# DC_Power_Switching.net
KiCad netlist of a schematic drawn in Altium Designer
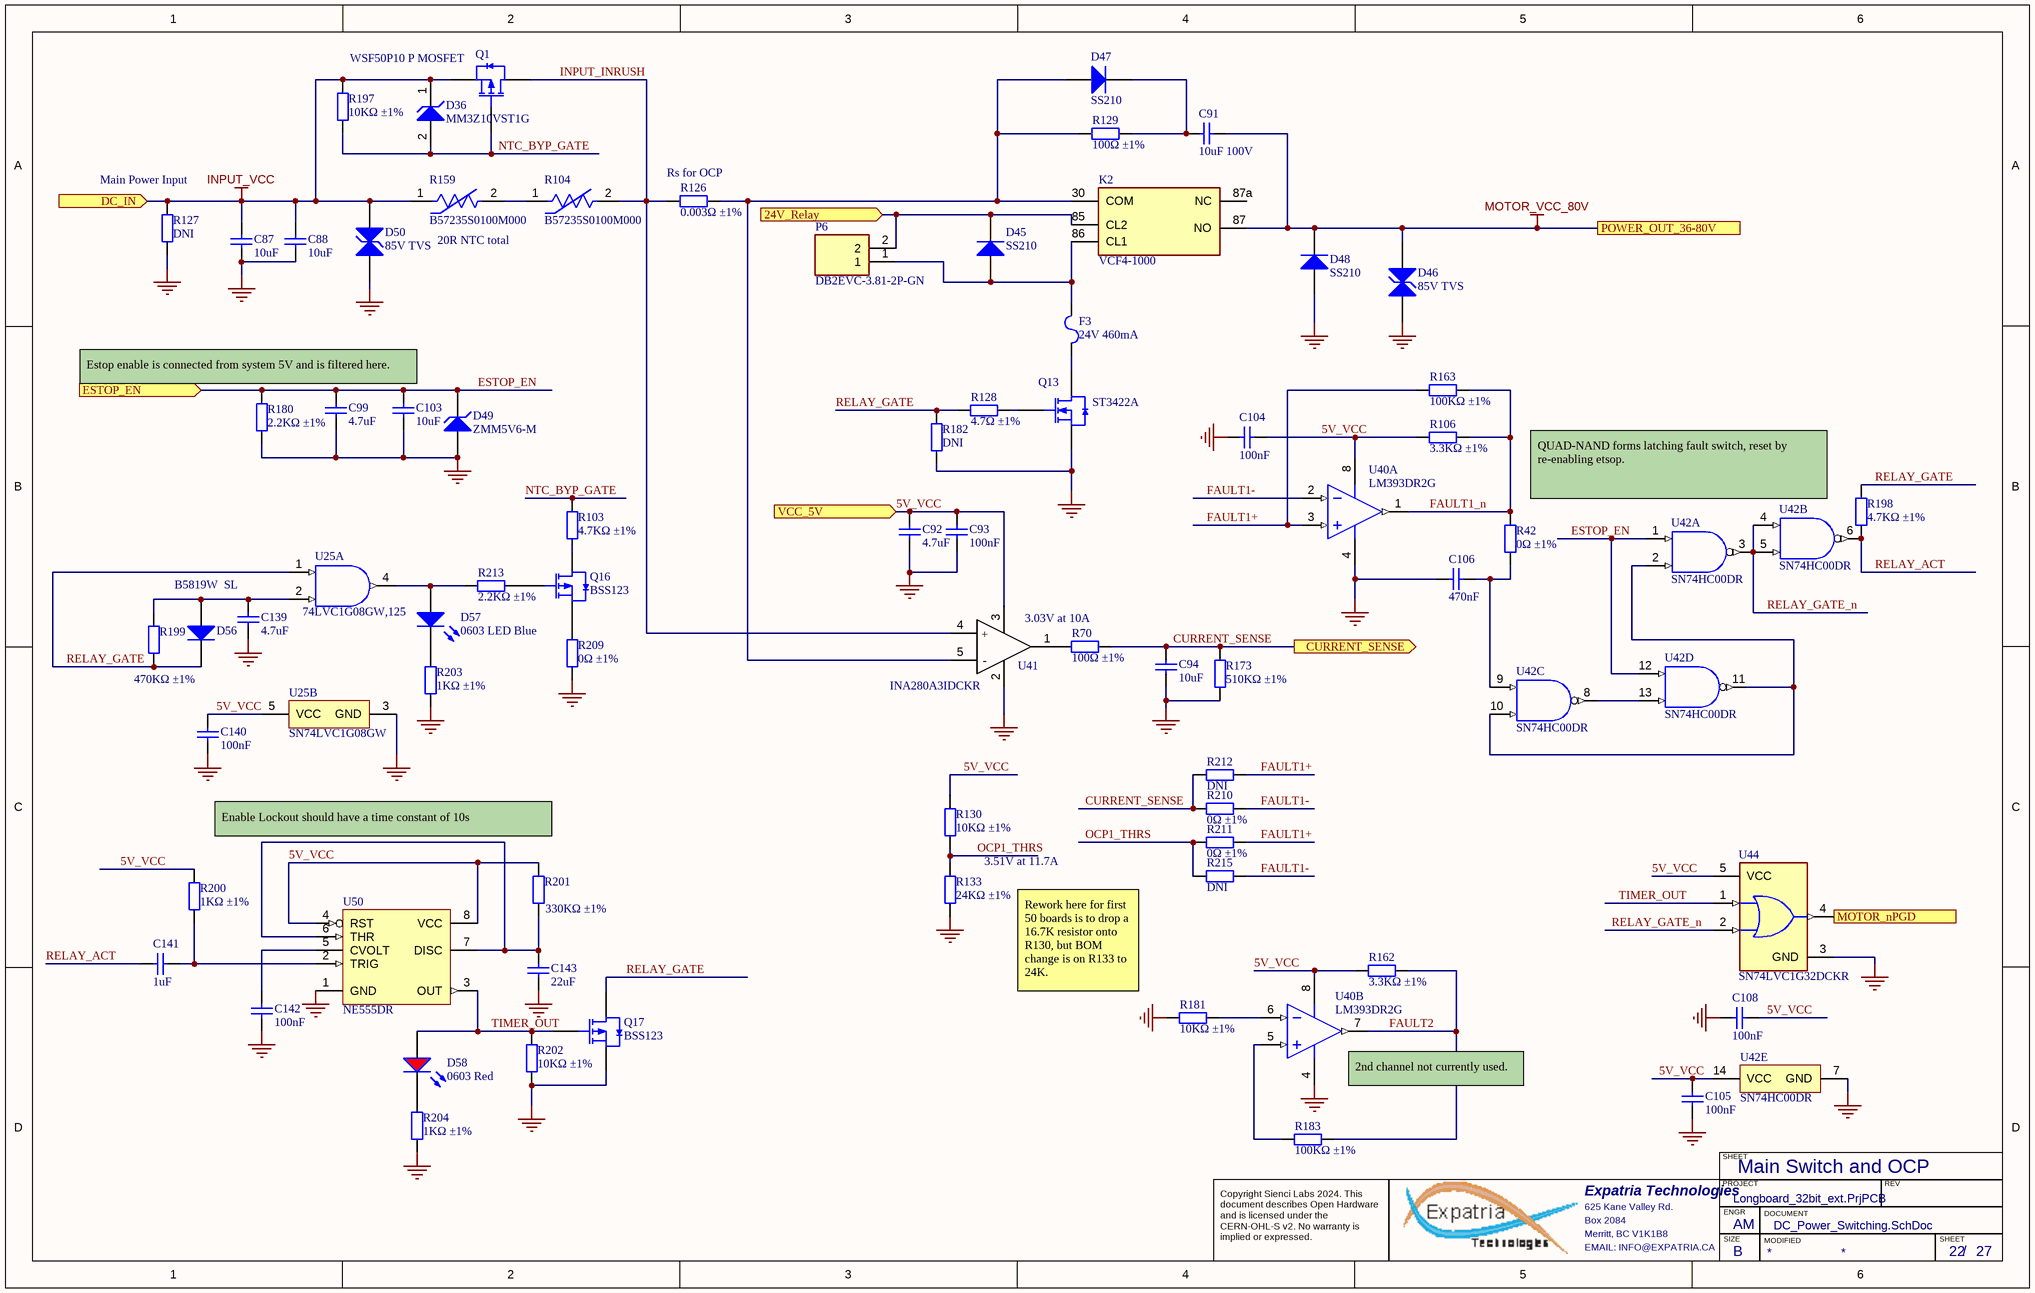
[diagram p0: DC_Power_Switching.SchDoc]

(export (version "E")
  (design (tool "Eeschema 10.0.6"))
  (components
    (comp (ref "C87")
      (value "10uF")
      (footprint "1206_C")
      (description "50V 10uF X5R ±10% 1206 Multilayer Ceramic Capacitors MLCC - SMD/SMT ROHS")
      (fields (field (name "MANUFACTURER") "Samsung Electro-Mechanics") (field (name "TOLERANCE") "10%"))
      (libsource (lib "Sienci_Labs") (part "1206 10uF (106) 10% 50V"))
    )
    (comp (ref "C88")
      (value "10uF")
      (footprint "1206_C")
      (description "50V 10uF X5R ±10% 1206 Multilayer Ceramic Capacitors MLCC - SMD/SMT ROHS")
      (fields (field (name "MANUFACTURER") "Samsung Electro-Mechanics") (field (name "TOLERANCE") "10%"))
      (libsource (lib "Sienci_Labs") (part "1206 10uF (106) 10% 50V"))
    )
    (comp (ref "C91")
      (value "10uF 100V")
      (footprint "1210_C")
      (description "Chip capacitors")
      (fields (field (name "MANUFACTURER") "Murata") (field (name "TOLERANCE") "10%"))
      (libsource (lib "Sienci_Labs") (part "1210 10uF (106) 10% 100V"))
    )
    (comp (ref "C92")
      (value "4.7uF")
      (footprint "0603_C")
      (description "16V 4.7uF X5R ±10% 0603 Multilayer Ceramic Capacitors MLCC - SMD/SMT ROHS")
      (fields (field (name "MANUFACTURER") "Samsung Electro-Mechanics") (field (name "TOLERANCE") "10%"))
      (libsource (lib "Sienci_Labs") (part "0603 4.7uF (475) 10% 16V"))
    )
    (comp (ref "C93")
      (value "100nF")
      (footprint "0603_C")
      (description "50V 100nF X7R ±10% 0603 Multilayer Ceramic Capacitors MLCC - SMD/SMT ROHS")
      (fields
        (field (name "MANUFACTURER") "YAGEO")
        (field (name "MANUFACTURER PART NUMBER") "CC0603KRX7R9BB104")
      )
      (libsource (lib "Sienci_Labs") (part "0603 100nF (104) 10% 50V"))
    )
    (comp (ref "C94")
      (value "10uF")
      (footprint "0603_C")
      (description "Chip capacitors")
      (fields (field (name "MANUFACTURER") "Samsung Electro-Mechanics") (field (name "TOLERANCE") "10%"))
      (libsource (lib "Cap") (part "0603 10uF (106) 10% 10V"))
    )
    (comp (ref "C99")
      (value "4.7uF")
      (footprint "0603_C")
      (description "16V 4.7uF X5R ±10% 0603 Multilayer Ceramic Capacitors MLCC - SMD/SMT ROHS")
      (fields (field (name "MANUFACTURER") "Samsung Electro-Mechanics") (field (name "TOLERANCE") "10%"))
      (libsource (lib "Sienci_Labs") (part "0603 4.7uF (475) 10% 16V"))
    )
    (comp (ref "C103")
      (value "10uF")
      (footprint "0603_C")
      (description "Chip capacitors")
      (fields
        (field (name "MANUFACTURER") "Samsung Electro-Mechanics")
        (field (name "MANUFACTURER PART NUMBER") "CL10A106KP8NNNC")
      )
      (libsource (lib "Cap") (part "0603 10uF (106) 10% 10V"))
    )
    (comp (ref "C104")
      (value "100nF")
      (footprint "0603_C")
      (description "50V 100nF X7R ±10% 0603 Multilayer Ceramic Capacitors MLCC - SMD/SMT ROHS")
      (fields
        (field (name "MANUFACTURER") "YAGEO")
        (field (name "MANUFACTURER PART NUMBER") "CC0603KRX7R9BB104")
      )
      (libsource (lib "Sienci_Labs") (part "0603 100nF (104) 10% 50V"))
    )
    (comp (ref "C105")
      (value "100nF")
      (footprint "0603_C")
      (description "50V 100nF X7R ±10% 0603 Multilayer Ceramic Capacitors MLCC - SMD/SMT ROHS")
      (fields
        (field (name "MANUFACTURER") "YAGEO")
        (field (name "MANUFACTURER PART NUMBER") "CC0603KRX7R9BB104")
      )
      (libsource (lib "Sienci_Labs") (part "0603 100nF (104) 10% 50V"))
    )
    (comp (ref "C106")
      (value "470nF")
      (footprint "0603_C")
      (description "Chip capacitors")
      (fields (field (name "MANUFACTURER") "Samsung Electro-Mechanics") (field (name "TOLERANCE") "10%"))
      (libsource (lib "Cap") (part "0603 470nF (474) 10% 25V"))
    )
    (comp (ref "C108")
      (value "100nF")
      (footprint "0603_C")
      (description "50V 100nF X7R ±10% 0603 Multilayer Ceramic Capacitors MLCC - SMD/SMT ROHS")
      (fields
        (field (name "MANUFACTURER") "YAGEO")
        (field (name "MANUFACTURER PART NUMBER") "CC0603KRX7R9BB104")
      )
      (libsource (lib "Sienci_Labs") (part "0603 100nF (104) 10% 50V"))
    )
    (comp (ref "C139")
      (value "4.7uF")
      (footprint "1206_C")
      (description "Chip capacitors")
      (fields
        (field (name "MANUFACTURER") "Guangdong Fenghua Advanced Tech")
        (field (name "MANUFACTURER PART NUMBER") "1206B475K500NT")
      )
      (libsource (lib "Cap") (part "1206 4.7uF (475) 10% 50V"))
    )
    (comp (ref "C140")
      (value "100nF")
      (footprint "0603_C")
      (description "50V 100nF X7R ±10% 0603 Multilayer Ceramic Capacitors MLCC - SMD/SMT ROHS")
      (fields
        (field (name "MANUFACTURER") "YAGEO")
        (field (name "MANUFACTURER PART NUMBER") "CC0603KRX7R9BB104")
      )
      (libsource (lib "Sienci_Labs") (part "0603 100nF (104) 10% 50V"))
    )
    (comp (ref "C141")
      (value "1uF")
      (footprint "0603_C")
      (description "Chip capacitors")
      (fields (field (name "MANUFACTURER") "Samsung Electro-Mechanics") (field (name "TOLERANCE") "10%"))
      (libsource (lib "Cap") (part "0603 1uF (105) 10% 50V"))
    )
    (comp (ref "C142")
      (value "100nF")
      (footprint "0603_C")
      (description "50V 100nF X7R ±10% 0603 Multilayer Ceramic Capacitors MLCC - SMD/SMT ROHS")
      (fields
        (field (name "MANUFACTURER") "YAGEO")
        (field (name "MANUFACTURER PART NUMBER") "CC0603KRX7R9BB104")
      )
      (libsource (lib "Sienci_Labs") (part "0603 100nF (104) 10% 50V"))
    )
    (comp (ref "C143")
      (value "22uF")
      (footprint "1206_C")
      (description "Chip capacitors")
      (fields
        (field (name "MANUFACTURER") "Samsung")
        (field (name "MANUFACTURER PART NUMBER") "CL31A226KAHNNNE")
      )
      (libsource (lib "Cap") (part "1206 4.7uF (475) 10% 50V"))
    )
    (comp (ref "D36")
      (value "MM3Z10VST1G")
      (footprint "ONSC-SOD-323-2-477-02_V")
      (description "MM3Z10VST1G Zener Diode, 10V 2% 300 mW SMT 2-Pin SOD-323 ¦ ON Semiconductor MM3Z10VST1G")
      (fields (field (name "MANUFACTURER") "On Semiconductor") (field (name "TOLERANCE") "2%"))
      (libsource (lib "Sienci_Labs") (part "MM3Z10VST1G"))
    )
    (comp (ref "D45")
      (value "SS210")
      (footprint "SMA(DO-214AC)_S1")
      (description "100V 2A 850mV @ 2A SMA(DO-214AC) Schottky Barrier Diodes (SBD) ROHS")
      (fields (field (name "MANUFACTURER") "MDD(Microdiode Electronics)"))
      (libsource (lib "Diode") (part "SMA(DO-214AC) SS210"))
    )
    (comp (ref "D46")
      (value "85V TVS")
      (footprint "SMB(DO-214AA)_S1")
      (description "4.4A 137V 94.4V 85V DO-214AA Electrostatic and Surge Protection (TVS/ESD) ROHS")
      (fields (field (name "MANUFACTURER") "BORN") (field (name "MANUFACTURER PART NUMBER") "SMBJ85CA"))
      (libsource (lib "Sienci_Labs") (part "SMBJ85CA"))
    )
    (comp (ref "D47")
      (value "SS210")
      (footprint "SMA(DO-214AC)_S1")
      (description "100V 2A 850mV @ 2A SMA(DO-214AC) Schottky Barrier Diodes (SBD) ROHS")
      (fields (field (name "MANUFACTURER") "MDD(Microdiode Electronics)"))
      (libsource (lib "Diode") (part "SMA(DO-214AC) SS210"))
    )
    (comp (ref "D48")
      (value "SS210")
      (footprint "SMA(DO-214AC)_S1")
      (description "100V 2A 850mV @ 2A SMA(DO-214AC) Schottky Barrier Diodes (SBD) ROHS")
      (fields (field (name "MANUFACTURER") "MDD(Microdiode Electronics)"))
      (libsource (lib "Diode") (part "SMA(DO-214AC) SS210"))
    )
    (comp (ref "D49")
      (value "ZMM5V6-M")
      (footprint "LL-34")
      (description "Single 500mW 5.2V~6V 5.6V LL-34 Zener Diodes ROHS")
      (fields (field (name "MANUFACTURER PART NUMBER") "ZMM5V6") (field (name "MANUFACTURER") "HXY MOSFET"))
      (libsource (lib "Sienci_Labs") (part "LL-34 ZMM5V6-M"))
    )
    (comp (ref "D50")
      (value "85V TVS")
      (footprint "SMB(DO-214AA)_S1")
      (description "4.4A 137V 94.4V 85V DO-214AA Electrostatic and Surge Protection (TVS/ESD) ROHS")
      (fields (field (name "MANUFACTURER") "BORN") (field (name "MANUFACTURER PART NUMBER") "SMBJ85CA"))
      (libsource (lib "Sienci_Labs") (part "SMBJ85CA"))
    )
    (comp (ref "D56")
      (value "B5819W  SL")
      (footprint "SOD-123")
      (description "40V 600mV@1A 1A SOD-123 Schottky Barrier Diodes (SBD) ROHS")
      (fields
        (field (name "MANUFACTURER") "Jiangsu Changjing Electronics Technology Co., Ltd.")
        (field (name "MANUFACTURER PART NUMBER") "B5819W SL")
      )
      (libsource (lib "Sienci_Labs") (part "B5819W  SL"))
    )
    (comp (ref "D57")
      (value "0603 LED Blue")
      (footprint "0603_LED_S1 - BLUE")
      (description "5mA -40℃~+85℃ Blue 120° 0603 Light Emitting Diodes (LED) ROHS")
      (fields
        (field (name "MANUFACTURER") "TUOZHAN")
        (field (name "MANUFACTURER PART NUMBER") "F.0603.00026/P2-0603B1TS2-06T-001")
      )
      (libsource (lib "Sienci_Labs") (part "0603 LED Blue"))
    )
    (comp (ref "D58")
      (value "0603 Red")
      (footprint "0603_LED_S1")
      (description "-40℃~+85℃ Red 0603 Light Emitting Diodes (LED) ROHS")
      (fields
        (field (name "MANUFACTURER") "Hubei KENTO Elec")
        (field (name "MANUFACTURER PART NUMBER") "KT-0603R")
      )
      (libsource (lib "Sienci_Labs") (part "KT-0603R"))
    )
    (comp (ref "F3")
      (value "24V 460mA")
      (footprint "1206_C")
      (description "24V 200mA 100A 460mA - Resettable Fuses ROHS")
      (fields
        (field (name "MANUFACTURER") "Jinrui Electronic Materials Co.")
        (field (name "PARTNUMBER") "JK-nSMD020-24")
      )
      (libsource (lib "PrintNC_GRBLHAL_Breakout") (part "JK-nSMD050-24"))
    )
    (comp (ref "K2")
      (value "VCF4-1000")
      (footprint "VCF41000")
      (description "RELAY SOCKET, 5 PIN, THROUGH HOLE; Available until stocks are exhausted Alternative available")
      (fields
        (field (name "MOUSER PART NUMBER") "655-VCF4-1000")
        (field (name "MANUFACTURER") "TE Connectivity")
      )
      (libsource (lib "Sienci_Labs") (part "VCF4-1000"))
    )
    (comp (ref "P6")
      (value "DB2EVC-3.81-2P-GN")
      (footprint "CONN-TH_5P-P3.81_DB2EVC-3.81-2p")
      (description "3.81mm Green Board Edge/Receptacle-Close Push-Pull,P=3.81mm Pluggable System Terminal Block ROHS")
      (fields (field (name "MANUFACTURER") "DIBO"))
      (libsource (lib "Sienci_Labs") (part "DB2EVC-3.81-2P-GN"))
    )
    (comp (ref "Q1")
      (value "WSF50P10 P MOSFET")
      (footprint "TO-252-2-180")
      (description "100V 34A 32mΩ@10V,18A 96W P Channel TO-252-2 MOSFETs ROHS")
      (fields
        (field (name "MANUFACTURER") "Winsok Semicon")
        (field (name "MANUFACTURER PART NUMBER") "WSF50P10")
      )
      (libsource (lib "MOS") (part "WSF50P10 P TO-252-2"))
    )
    (comp (ref "Q13")
      (value "ST3422A")
      (footprint "SOT-23-3L")
      (fields (field (name "MANUFACTURER") "STANSON Tech."))
      (libsource (lib "Sienci_Labs") (part "ST3422A"))
    )
    (comp (ref "Q16")
      (value "BSS123")
      (footprint "SOT-23-3L")
      (description "100V 170mA 6Ω@10V 350mW 2.5V@250uA N Channel SOT-23 MOSFETs ROHS")
      (fields (field (name "MANUFACTURER") "HXY MOSFET"))
      (libsource (lib "MOS") (part "BSS123"))
    )
    (comp (ref "Q17")
      (value "BSS123")
      (footprint "SOT-23-3L")
      (description "100V 170mA 6Ω@10V 350mW 2.5V@250uA N Channel SOT-23 MOSFETs ROHS")
      (fields (field (name "MANUFACTURER") "HXY MOSFET"))
      (libsource (lib "MOS") (part "BSS123"))
    )
    (comp (ref "R42")
      (value "0Ω ±1%")
      (footprint "0603_R")
      (description "Chip resistor")
      (fields (field (name "MANUFACTURER") "Uniroyal Elec") (field (name "POWER") "1/10W"))
      (libsource (lib "") (part "0603 0R (0R0) 1%_1"))
    )
    (comp (ref "R70")
      (value "100Ω ±1%")
      (footprint "0603_R")
      (description "Chip resistor")
      (fields (field (name "MANUFACTURER") "Uniroyal Elec") (field (name "POWER") "1/10W"))
      (libsource (lib "RES") (part "0603 100R (1000) 1%"))
    )
    (comp (ref "R103")
      (value "4.7KΩ ±1%")
      (footprint "0603_R")
      (description "Chip resistor")
      (fields
        (field (name "MANUFACTURER") "Uniroyal Elec")
        (field (name "MANUFACTURER PART NUMBER") "0603WAF4701T5E")
      )
      (libsource (lib "RES") (part "0603 4.7K (4701) 1%"))
    )
    (comp (ref "R104")
      (value "B57235S0100M000")
      (footprint "RES-TH_L9.5-W6.0-P5.00-D0.6")
      (description "Inrush Current Limiter 10 Ohms ±20% 3A 0.374\" (9.50mm)")
      (fields (field (name "MANUFACTURER") "TDK"))
      (libsource (lib "Universal_CNC_Breakout") (part "B57235S0259M000"))
    )
    (comp (ref "R106")
      (value "3.3KΩ ±1%")
      (footprint "0603_R")
      (description "Chip resistor")
      (fields
        (field (name "MANUFACTURER") "Uniroyal Elec")
        (field (name "MANUFACTURER PART NUMBER") "0603WAF3301T5E")
      )
      (libsource (lib "RES") (part "0603 3.3K (3301) 1%"))
    )
    (comp (ref "R126")
      (value "0.003Ω ±1%")
      (footprint "1206_R")
      (description "Chip Resistor")
      (fields
        (field (name "MANUFACTURER") "Vishay")
        (field (name "MANUFACTURER PART NUMBER") "WFC12063L000FE66")
      )
      (libsource (lib "RES") (part "1206 0.003R (R50) 1%"))
    )
    (comp (ref "R127")
      (value "DNI")
      (footprint "0603_R")
      (description "Chip resistor")
      (fields (field (name "MANUFACTURER") "Uniroyal Elec") (field (name "POWER") "1/10W"))
      (libsource (lib "Sienci_Labs") (part "0603 10K (1002) 1%"))
    )
    (comp (ref "R128")
      (value "4.7Ω ±1%")
      (footprint "0603_R")
      (description "Chip resistor")
      (fields
        (field (name "MANUFACTURER") "Uniroyal Elec")
        (field (name "MANUFACTURER PART NUMBER") "0603WAF470KT5E")
      )
      (libsource (lib "RES") (part "0603 4.7R (4R70) 1%"))
    )
    (comp (ref "R129")
      (value "100Ω ±1%")
      (footprint "1206_R")
      (description "Chip resistor")
      (fields
        (field (name "MANUFACTURER") "Uniroyal Elec")
        (field (name "MANUFACTURER PART NUMBER") "1206W4F1000T5E")
      )
      (libsource (lib "RES") (part "1206 100R (1000) 1%"))
    )
    (comp (ref "R130")
      (value "10KΩ ±1%")
      (footprint "0603_R")
      (description "Chip resistor")
      (fields (field (name "MANUFACTURER") "Uniroyal Elec") (field (name "POWER") "1/10W"))
      (libsource (lib "Sienci_Labs") (part "0603 10K (1002) 1%"))
    )
    (comp (ref "R133")
      (value "24KΩ ±1%")
      (footprint "0603_R")
      (description "Chip resistor")
      (fields (field (name "MANUFACTURER") "Uniroyal Elec") (field (name "POWER") "1/10W"))
      (libsource (lib "RES") (part "0603 24K (2402) 1%"))
    )
    (comp (ref "R159")
      (value "B57235S0100M000")
      (footprint "RES-TH_L9.5-W6.0-P5.00-D0.6")
      (description "Inrush Current Limiter 10 Ohms ±20% 3A 0.374\" (9.50mm)")
      (fields (field (name "MANUFACTURER") "TDK"))
      (libsource (lib "Universal_CNC_Breakout") (part "B57235S0259M000"))
    )
    (comp (ref "R162")
      (value "3.3KΩ ±1%")
      (footprint "0603_R")
      (description "Chip resistor")
      (fields
        (field (name "MANUFACTURER") "Uniroyal Elec")
        (field (name "MANUFACTURER PART NUMBER") "0603WAF3301T5E")
      )
      (libsource (lib "RES") (part "0603 3.3K (3301) 1%"))
    )
    (comp (ref "R163")
      (value "100KΩ ±1%")
      (footprint "0603_R")
      (description "Chip resistor")
      (fields
        (field (name "MANUFACTURER") "Uniroyal Elec")
        (field (name "MANUFACTURER PART NUMBER") "0603WAF1003T5E")
      )
      (libsource (lib "RES") (part "0603 100K (1003) 1%"))
    )
    (comp (ref "R173")
      (value "510KΩ ±1%")
      (footprint "0603_R")
      (description "Chip resistor")
      (fields
        (field (name "MANUFACTURER") "Uniroyal Elec")
        (field (name "MANUFACTURER PART NUMBER") "0603WAF5103T5E")
      )
      (libsource (lib "RES") (part "0603 510K (5103) 1%"))
    )
    (comp (ref "R180")
      (value "2.2KΩ ±1%")
      (footprint "0603_R")
      (description "Chip resistor")
      (fields
        (field (name "MANUFACTURER") "Uniroyal Elec")
        (field (name "MANUFACTURER PART NUMBER") "0603WAF2201T5E")
      )
      (libsource (lib "RES") (part "0603 2.2K (2201) 1%"))
    )
    (comp (ref "R181")
      (value "10KΩ ±1%")
      (footprint "0603_R")
      (description "Chip resistor")
      (fields (field (name "MANUFACTURER") "Uniroyal Elec") (field (name "POWER") "1/10W"))
      (libsource (lib "") (part "0603 10K (1002) 1%_1"))
    )
    (comp (ref "R182")
      (value "DNI")
      (footprint "0603_R")
      (description "Chip resistor")
      (fields (field (name "MANUFACTURER") "Uniroyal Elec") (field (name "POWER") "1/10W"))
      (libsource (lib "Sienci_Labs") (part "0603 10K (1002) 1%"))
    )
    (comp (ref "R183")
      (value "100KΩ ±1%")
      (footprint "0603_R")
      (description "Chip resistor")
      (fields
        (field (name "MANUFACTURER") "Uniroyal Elec")
        (field (name "MANUFACTURER PART NUMBER") "0603WAF1003T5E")
      )
      (libsource (lib "RES") (part "0603 100K (1003) 1%"))
    )
    (comp (ref "R197")
      (value "10KΩ ±1%")
      (footprint "0603_R")
      (description "Chip resistor")
      (fields (field (name "MANUFACTURER") "Uniroyal Elec") (field (name "POWER") "1/10W"))
      (libsource (lib "Sienci_Labs") (part "0603 10K (1002) 1%"))
    )
    (comp (ref "R198")
      (value "4.7KΩ ±1%")
      (footprint "0603_R")
      (description "Chip resistor")
      (fields
        (field (name "MANUFACTURER") "Uniroyal Elec")
        (field (name "MANUFACTURER PART NUMBER") "0603WAF4701T5E")
      )
      (libsource (lib "RES") (part "0603 4.7K (4701) 1%"))
    )
    (comp (ref "R199")
      (value "470KΩ ±1%")
      (footprint "0603_R")
      (description "Chip resistor")
      (fields
        (field (name "MANUFACTURER") "Uniroyal Elec")
        (field (name "MANUFACTURER PART NUMBER") "0603WAF4703T5E")
      )
      (libsource (lib "RES") (part "0603 470K (4703) 1%"))
    )
    (comp (ref "R200")
      (value "1KΩ ±1%")
      (footprint "0603_R")
      (description "Chip resistor")
      (fields (field (name "MANUFACTURER") "Uniroyal Elec") (field (name "POWER") "1/10W"))
      (libsource (lib "Sienci_Labs") (part "0603 1K (1001) 1%"))
    )
    (comp (ref "R201")
      (value "330KΩ ±1%")
      (footprint "0603_R")
      (description "Chip resistor")
      (fields
        (field (name "MANUFACTURER") "Uniroyal Elec")
        (field (name "MANUFACTURER PART NUMBER") "0603WAF3303T5E")
      )
      (libsource (lib "RES") (part "0603 330K (3303) 1%"))
    )
    (comp (ref "R202")
      (value "10KΩ ±1%")
      (footprint "0603_R")
      (description "Chip resistor")
      (fields (field (name "MANUFACTURER") "Uniroyal Elec") (field (name "POWER") "1/10W"))
      (libsource (lib "Sienci_Labs") (part "0603 10K (1002) 1%"))
    )
    (comp (ref "R203")
      (value "1KΩ ±1%")
      (footprint "0603_R")
      (description "Chip resistor")
      (fields (field (name "MANUFACTURER") "Uniroyal Elec") (field (name "POWER") "1/10W"))
      (libsource (lib "Sienci_Labs") (part "0603 1K (1001) 1%"))
    )
    (comp (ref "R204")
      (value "1KΩ ±1%")
      (footprint "0603_R")
      (description "Chip resistor")
      (fields (field (name "MANUFACTURER") "Uniroyal Elec") (field (name "POWER") "1/10W"))
      (libsource (lib "Sienci_Labs") (part "0603 1K (1001) 1%"))
    )
    (comp (ref "R209")
      (value "0Ω ±1%")
      (footprint "0603_R")
      (description "Chip resistor")
      (fields (field (name "MANUFACTURER") "Uniroyal Elec") (field (name "POWER") "1/10W"))
      (libsource (lib "") (part "0603 0R (0R0) 1%_1"))
    )
    (comp (ref "R210")
      (value "0Ω ±1%")
      (footprint "0603_R")
      (description "Chip resistor")
      (fields (field (name "MANUFACTURER") "Uniroyal Elec") (field (name "POWER") "1/10W"))
      (libsource (lib "Sienci_Labs") (part "0603 0R (0R0) 1%"))
    )
    (comp (ref "R211")
      (value "0Ω ±1%")
      (footprint "0603_R")
      (description "Chip resistor")
      (fields (field (name "MANUFACTURER") "Uniroyal Elec") (field (name "POWER") "1/10W"))
      (libsource (lib "Sienci_Labs") (part "0603 0R (0R0) 1%"))
    )
    (comp (ref "R212")
      (value "DNI")
      (footprint "0603_R")
      (description "Chip resistor")
      (fields (field (name "MANUFACTURER") "Uniroyal Elec") (field (name "POWER") "1/10W"))
      (libsource (lib "Sienci_Labs") (part "0603 0R (0R0) 1%"))
    )
    (comp (ref "R213")
      (value "2.2KΩ ±1%")
      (footprint "0603_R")
      (description "Chip resistor")
      (fields
        (field (name "MANUFACTURER") "Uniroyal Elec")
        (field (name "MANUFACTURER PART NUMBER") "0603WAF2201T5E")
      )
      (libsource (lib "") (part "0603 2.2K (2201) 1%_1"))
    )
    (comp (ref "R215")
      (value "DNI")
      (footprint "0603_R")
      (description "Chip resistor")
      (fields (field (name "MANUFACTURER") "Uniroyal Elec") (field (name "POWER") "1/10W"))
      (libsource (lib "Sienci_Labs") (part "0603 0R (0R0) 1%"))
    )
    (comp (ref "U25")
      (value "74LVC1G08GW,125")
      (footprint "DCK0005A_M")
      (description "Single 2-Input Positive-AND Gate, DCK0005A")
      (fields (field (name "GENERIC PART NUMBER") "SN74LVC1G08") (field (name "MANUFACTURER") "Nexperia"))
      (libsource (lib "Altium Content Vault") (part "TI-SN74XXX1X08-5"))
    )
    (comp (ref "U40")
      (value "LM393DR2G")
      (footprint "SOIC-8_150mil")
      (description "IC COMPARATOR DUAL OFFSET LV 8SOIC")
      (fields (field (name "MANUFACTURER") "onsemi"))
      (libsource (lib "IC") (part "LM393DR2G_[C7955]"))
    )
    (comp (ref "U41")
      (value "INA280A3IDCKR")
      (footprint "SOT65P210X110-5N")
      (fields (field (name "MANUFACTURER") "Texas Instruments"))
      (libsource (lib "Sienci_Labs") (part "INA280A3IDCKR"))
    )
    (comp (ref "U42")
      (value "SN74HC00DR")
      (footprint "D0014A_L")
      (description "4-ch, 2-input, 2-V to 6-V 5.2 mA drive strength NAND gate 14-SOIC -40 to 85")
      (fields
        (field (name "GENERIC PART NUMBER") "SN74HC00")
        (field (name "MANUFACTURER") "Texas Instruments")
      )
      (libsource (lib "Sienci_Labs") (part "SN74HC00DR"))
    )
    (comp (ref "U44")
      (value "SN74LVC1G32DCKR")
      (footprint "FP-DCK0005A-IPC_A")
      (description "1-ch, 2-input 1.65-V to 5.5-V 32-mA drive strength OR gate 5-SC70 -40 to 125")
      (fields (field (name "MANUFACTURER") "Texas Instruments"))
      (libsource (lib "Sienci_Labs") (part "SN74LVC1G32DCKR"))
    )
    (comp (ref "U50")
      (value "NE555DR")
      (footprint "SOIC-8_150mil")
      (description "100kHz SOIC-8 Timers / Clock Oscillators ROHS")
      (fields (field (name "MANUFACTURER") "Texas Instruments"))
      (libsource (lib "IC") (part "NE555DR_[C7593]"))
    )
  )
  (nets
    (net (code "1") (name "/5V_VCC") (class "Default")
      (node (ref "C104") (pin "2") (pinfunction "2_2") (pintype "passive"))
      (node (ref "C105") (pin "2") (pinfunction "2_2") (pintype "passive"))
      (node (ref "C108") (pin "2") (pinfunction "2_2") (pintype "passive"))
      (node (ref "C140") (pin "2") (pinfunction "2_2") (pintype "passive"))
      (node (ref "C92") (pin "2") (pinfunction "2_2") (pintype "passive"))
      (node (ref "C93") (pin "2") (pinfunction "2_2") (pintype "passive"))
      (node (ref "R106") (pin "2") (pinfunction "2_2") (pintype "passive"))
      (node (ref "R130") (pin "2") (pinfunction "2_2") (pintype "passive"))
      (node (ref "R162") (pin "2") (pinfunction "2_2") (pintype "passive"))
      (node (ref "R200") (pin "2") (pinfunction "2_2") (pintype "passive"))
      (node (ref "R201") (pin "2") (pinfunction "2_2") (pintype "passive"))
      (node (ref "U25") (pin "5") (pinfunction "VCC_5") (pintype "power_in"))
      (node (ref "U40") (pin "8") (pinfunction "V+_8") (pintype "power_in"))
      (node (ref "U41") (pin "3") (pinfunction "VS_3") (pintype "power_in"))
      (node (ref "U42") (pin "14") (pinfunction "VCC_14") (pintype "power_in"))
      (node (ref "U44") (pin "5") (pinfunction "VCC_5") (pintype "power_in"))
      (node (ref "U50") (pin "4") (pinfunction "RST_4") (pintype "input"))
      (node (ref "U50") (pin "8") (pinfunction "VCC_8") (pintype "power_in"))
    )
    (net (code "2") (name "/24V_Relay") (class "Default")
      (node (ref "D45") (pin "2") (pinfunction "K_2") (pintype "passive"))
      (node (ref "K2") (pin "85") (pinfunction "CL2_85") (pintype "passive"))
      (node (ref "P6") (pin "2") (pinfunction "2_2") (pintype "passive"))
    )
    (net (code "3") (name "/CURRENT_SENSE") (class "Default")
      (node (ref "C94") (pin "2") (pinfunction "2_2") (pintype "passive"))
      (node (ref "R173") (pin "2") (pinfunction "2_2") (pintype "passive"))
      (node (ref "R210") (pin "2") (pinfunction "2_2") (pintype "passive"))
      (node (ref "R212") (pin "2") (pinfunction "2_2") (pintype "passive"))
      (node (ref "R70") (pin "2") (pinfunction "2_2") (pintype "passive"))
    )
    (net (code "4") (name "/ESTOP_EN") (class "Default")
      (node (ref "C103") (pin "2") (pinfunction "2_2") (pintype "passive"))
      (node (ref "C99") (pin "2") (pinfunction "2_2") (pintype "passive"))
      (node (ref "D49") (pin "2") (pinfunction "K_2") (pintype "passive"))
      (node (ref "R180") (pin "2") (pinfunction "2_2") (pintype "passive"))
      (node (ref "U42") (pin "1") (pinfunction "1A_1") (pintype "input"))
      (node (ref "U42") (pin "12") (pinfunction "4A_12") (pintype "input"))
    )
    (net (code "5") (name "/FAULT1+") (class "Default")
      (node (ref "R163") (pin "1") (pinfunction "1_1") (pintype "passive"))
      (node (ref "R211") (pin "1") (pinfunction "1_1") (pintype "passive"))
      (node (ref "R212") (pin "1") (pinfunction "1_1") (pintype "passive"))
      (node (ref "U40") (pin "3") (pinfunction "IN+_3") (pintype "input"))
    )
    (net (code "6") (name "/FAULT1-") (class "Default")
      (node (ref "R210") (pin "1") (pinfunction "1_1") (pintype "passive"))
      (node (ref "R215") (pin "1") (pinfunction "1_1") (pintype "passive"))
      (node (ref "U40") (pin "2") (pinfunction "IN-_2") (pintype "input"))
    )
    (net (code "7") (name "/FAULT1_n") (class "Default")
      (node (ref "R106") (pin "1") (pinfunction "1_1") (pintype "passive"))
      (node (ref "R163") (pin "2") (pinfunction "2_2") (pintype "passive"))
      (node (ref "R42") (pin "2") (pinfunction "2_2") (pintype "passive"))
      (node (ref "U40") (pin "1") (pinfunction "OUT_1") (pintype "output"))
    )
    (net (code "8") (name "/FAULT2") (class "Default")
      (node (ref "R162") (pin "1") (pinfunction "1_1") (pintype "passive"))
      (node (ref "R183") (pin "2") (pinfunction "2_2") (pintype "passive"))
      (node (ref "U40") (pin "7") (pinfunction "OUT_7") (pintype "output"))
    )
    (net (code "9") (name "/INPUT_INRUSH") (class "Default")
      (node (ref "Q1") (pin "2") (pinfunction "D_2") (pintype "passive"))
      (node (ref "R104") (pin "2") (pinfunction "2_2") (pintype "passive"))
      (node (ref "R126") (pin "2") (pinfunction "2_2") (pintype "passive"))
      (node (ref "U41") (pin "4") (pinfunction "IN+_4") (pintype "tri_state"))
    )
    (net (code "10") (name "/MOTOR_nPGD") (class "Default")
      (node (ref "U44") (pin "4") (pinfunction "Y_4") (pintype "output"))
    )
    (net (code "11") (name "/NTC_BYP_GATE") (class "Default")
      (node (ref "D36") (pin "2") (pinfunction "A_2") (pintype "passive"))
      (node (ref "Q1") (pin "1") (pinfunction "G_1") (pintype "passive"))
      (node (ref "R103") (pin "2") (pinfunction "2_2") (pintype "passive"))
      (node (ref "R197") (pin "1") (pinfunction "1_1") (pintype "passive"))
    )
    (net (code "12") (name "/OCP1_THRS") (class "Default")
      (node (ref "R130") (pin "1") (pinfunction "1_1") (pintype "passive"))
      (node (ref "R133") (pin "2") (pinfunction "2_2") (pintype "passive"))
      (node (ref "R211") (pin "2") (pinfunction "2_2") (pintype "passive"))
      (node (ref "R215") (pin "2") (pinfunction "2_2") (pintype "passive"))
    )
    (net (code "13") (name "/RELAY_ACT") (class "Default")
      (node (ref "C141") (pin "2") (pinfunction "2_2") (pintype "passive"))
      (node (ref "R198") (pin "1") (pinfunction "1_1") (pintype "passive"))
      (node (ref "U42") (pin "6") (pinfunction "2Y_6") (pintype "output"))
    )
    (net (code "14") (name "/RELAY_GATE") (class "Default")
      (node (ref "D56") (pin "2") (pinfunction "K_2") (pintype "passive"))
      (node (ref "Q17") (pin "3") (pinfunction "D_3") (pintype "passive"))
      (node (ref "R128") (pin "1") (pinfunction "1_1") (pintype "passive"))
      (node (ref "R182") (pin "2") (pinfunction "2_2") (pintype "passive"))
      (node (ref "R198") (pin "2") (pinfunction "2_2") (pintype "passive"))
      (node (ref "R199") (pin "1") (pinfunction "1_1") (pintype "passive"))
      (node (ref "U25") (pin "1") (pinfunction "A_1") (pintype "input"))
    )
    (net (code "15") (name "/RELAY_GATE_n") (class "Default")
      (node (ref "U42") (pin "3") (pinfunction "1Y_3") (pintype "output"))
      (node (ref "U42") (pin "4") (pinfunction "2A_4") (pintype "input"))
      (node (ref "U42") (pin "5") (pinfunction "2B_5") (pintype "input"))
      (node (ref "U44") (pin "2") (pinfunction "B_2") (pintype "input"))
    )
    (net (code "16") (name "/TIMER_OUT") (class "Default")
      (node (ref "D58") (pin "A") (pinfunction "A_A") (pintype "passive"))
      (node (ref "Q17") (pin "1") (pinfunction "G_1") (pintype "passive"))
      (node (ref "R202") (pin "2") (pinfunction "2_2") (pintype "passive"))
      (node (ref "U44") (pin "1") (pinfunction "A_1") (pintype "input"))
      (node (ref "U50") (pin "3") (pinfunction "OUT_3") (pintype "output"))
    )
    (net (code "17") (name "GND") (class "Default")
      (node (ref "C103") (pin "1") (pinfunction "1_1") (pintype "passive"))
      (node (ref "C104") (pin "1") (pinfunction "1_1") (pintype "passive"))
      (node (ref "C105") (pin "1") (pinfunction "1_1") (pintype "passive"))
      (node (ref "C106") (pin "2") (pinfunction "2_2") (pintype "passive"))
      (node (ref "C108") (pin "1") (pinfunction "1_1") (pintype "passive"))
      (node (ref "C139") (pin "1") (pinfunction "1_1") (pintype "passive"))
      (node (ref "C140") (pin "1") (pinfunction "1_1") (pintype "passive"))
      (node (ref "C142") (pin "1") (pinfunction "1_1") (pintype "passive"))
      (node (ref "C143") (pin "1") (pinfunction "1_1") (pintype "passive"))
      (node (ref "C87") (pin "1") (pinfunction "1_1") (pintype "passive"))
      (node (ref "C88") (pin "1") (pinfunction "1_1") (pintype "passive"))
      (node (ref "C92") (pin "1") (pinfunction "1_1") (pintype "passive"))
      (node (ref "C93") (pin "1") (pinfunction "1_1") (pintype "passive"))
      (node (ref "C94") (pin "1") (pinfunction "1_1") (pintype "passive"))
      (node (ref "C99") (pin "1") (pinfunction "1_1") (pintype "passive"))
      (node (ref "D46") (pin "1") (pinfunction "A_1") (pintype "passive"))
      (node (ref "D48") (pin "1") (pinfunction "A_1") (pintype "passive"))
      (node (ref "D49") (pin "1") (pinfunction "A_1") (pintype "passive"))
      (node (ref "D50") (pin "1") (pinfunction "A_1") (pintype "passive"))
      (node (ref "Q13") (pin "2") (pinfunction "S_2") (pintype "passive"))
      (node (ref "Q17") (pin "2") (pinfunction "S_2") (pintype "passive"))
      (node (ref "R127") (pin "1") (pinfunction "1_1") (pintype "passive"))
      (node (ref "R133") (pin "1") (pinfunction "1_1") (pintype "passive"))
      (node (ref "R173") (pin "1") (pinfunction "1_1") (pintype "passive"))
      (node (ref "R180") (pin "1") (pinfunction "1_1") (pintype "passive"))
      (node (ref "R181") (pin "2") (pinfunction "2_2") (pintype "passive"))
      (node (ref "R182") (pin "1") (pinfunction "1_1") (pintype "passive"))
      (node (ref "R202") (pin "1") (pinfunction "1_1") (pintype "passive"))
      (node (ref "R203") (pin "1") (pinfunction "1_1") (pintype "passive"))
      (node (ref "R204") (pin "1") (pinfunction "1_1") (pintype "passive"))
      (node (ref "R209") (pin "1") (pinfunction "1_1") (pintype "passive"))
      (node (ref "U25") (pin "3") (pinfunction "GND_3") (pintype "power_in"))
      (node (ref "U40") (pin "4") (pinfunction "GND_4") (pintype "power_in"))
      (node (ref "U41") (pin "2") (pinfunction "GND_2") (pintype "power_in"))
      (node (ref "U42") (pin "7") (pinfunction "GND_7") (pintype "power_in"))
      (node (ref "U44") (pin "3") (pinfunction "GND_3") (pintype "power_in"))
      (node (ref "U50") (pin "1") (pinfunction "GND_1") (pintype "power_in"))
    )
    (net (code "18") (name "INPUT_VCC") (class "Default")
      (node (ref "C87") (pin "2") (pinfunction "2_2") (pintype "passive"))
      (node (ref "C88") (pin "2") (pinfunction "2_2") (pintype "passive"))
      (node (ref "D36") (pin "1") (pinfunction "K_1") (pintype "passive"))
      (node (ref "D50") (pin "2") (pinfunction "K_2") (pintype "passive"))
      (node (ref "Q1") (pin "3") (pinfunction "S_3") (pintype "passive"))
      (node (ref "R127") (pin "2") (pinfunction "2_2") (pintype "passive"))
      (node (ref "R159") (pin "1") (pinfunction "1_1") (pintype "passive"))
      (node (ref "R197") (pin "2") (pinfunction "2_2") (pintype "passive"))
    )
    (net (code "19") (name "MOTOR_VCC_80V") (class "Default")
      (node (ref "C91") (pin "2") (pinfunction "2_2") (pintype "passive"))
      (node (ref "D46") (pin "2") (pinfunction "K_2") (pintype "passive"))
      (node (ref "D48") (pin "2") (pinfunction "K_2") (pintype "passive"))
      (node (ref "K2") (pin "87") (pinfunction "NO_87") (pintype "passive"))
    )
    (net (code "20") (name "Net-(D45-A)") (class "Default")
      (node (ref "D45") (pin "1") (pinfunction "A_1") (pintype "passive"))
      (node (ref "F3") (pin "2") (pinfunction "2_2") (pintype "passive"))
      (node (ref "K2") (pin "86") (pinfunction "CL1_86") (pintype "passive"))
      (node (ref "P6") (pin "1") (pinfunction "1_1") (pintype "passive"))
    )
    (net (code "21") (name "Net-(D47-A)") (class "Default")
      (node (ref "D47") (pin "1") (pinfunction "A_1") (pintype "passive"))
      (node (ref "K2") (pin "30") (pinfunction "COM_30") (pintype "passive"))
      (node (ref "R126") (pin "1") (pinfunction "1_1") (pintype "passive"))
      (node (ref "R129") (pin "1") (pinfunction "1_1") (pintype "passive"))
      (node (ref "U41") (pin "5") (pinfunction "IN-_5") (pintype "tri_state"))
    )
    (net (code "22") (name "Net-(D47-K)") (class "Default")
      (node (ref "C91") (pin "1") (pinfunction "1_1") (pintype "passive"))
      (node (ref "D47") (pin "2") (pinfunction "K_2") (pintype "passive"))
      (node (ref "R129") (pin "2") (pinfunction "2_2") (pintype "passive"))
    )
    (net (code "23") (name "Net-(D56-A)") (class "Default")
      (node (ref "C139") (pin "2") (pinfunction "2_2") (pintype "passive"))
      (node (ref "D56") (pin "1") (pinfunction "A_1") (pintype "passive"))
      (node (ref "R199") (pin "2") (pinfunction "2_2") (pintype "passive"))
      (node (ref "U25") (pin "2") (pinfunction "B_2") (pintype "input"))
    )
    (net (code "24") (name "Net-(D57-PadK)") (class "Default")
      (node (ref "D57") (pin "K") (pinfunction "K_K") (pintype "passive"))
      (node (ref "R203") (pin "2") (pinfunction "2_2") (pintype "passive"))
    )
    (net (code "25") (name "Net-(D58-PadK)") (class "Default")
      (node (ref "D58") (pin "K") (pinfunction "K_K") (pintype "passive"))
      (node (ref "R204") (pin "2") (pinfunction "2_2") (pintype "passive"))
    )
    (net (code "26") (name "Net-(Q13-D)") (class "Default")
      (node (ref "F3") (pin "1") (pinfunction "1_1") (pintype "passive"))
      (node (ref "Q13") (pin "3") (pinfunction "D_3") (pintype "passive"))
    )
    (net (code "27") (name "Net-(Q13-G)") (class "Default")
      (node (ref "Q13") (pin "1") (pinfunction "G_1") (pintype "passive"))
      (node (ref "R128") (pin "2") (pinfunction "2_2") (pintype "passive"))
    )
    (net (code "28") (name "Net-(Q16-D)") (class "Default")
      (node (ref "Q16") (pin "3") (pinfunction "D_3") (pintype "passive"))
      (node (ref "R103") (pin "1") (pinfunction "1_1") (pintype "passive"))
    )
    (net (code "29") (name "Net-(Q16-G)") (class "Default")
      (node (ref "Q16") (pin "1") (pinfunction "G_1") (pintype "passive"))
      (node (ref "R213") (pin "1") (pinfunction "1_1") (pintype "passive"))
    )
    (net (code "30") (name "Net-(Q16-S)") (class "Default")
      (node (ref "Q16") (pin "2") (pinfunction "S_2") (pintype "passive"))
      (node (ref "R209") (pin "2") (pinfunction "2_2") (pintype "passive"))
    )
    (net (code "31") (name "Net-(R104-Pad1)") (class "Default")
      (node (ref "R104") (pin "1") (pinfunction "1_1") (pintype "passive"))
      (node (ref "R159") (pin "2") (pinfunction "2_2") (pintype "passive"))
    )
    (net (code "32") (name "Net-(U25A-Y)") (class "Default")
      (node (ref "D57") (pin "A") (pinfunction "A_A") (pintype "passive"))
      (node (ref "R213") (pin "2") (pinfunction "2_2") (pintype "passive"))
      (node (ref "U25") (pin "4") (pinfunction "Y_4") (pintype "output"))
    )
    (net (code "33") (name "Net-(U40B-IN+)") (class "Default")
      (node (ref "R183") (pin "1") (pinfunction "1_1") (pintype "passive"))
      (node (ref "U40") (pin "5") (pinfunction "IN+_5") (pintype "input"))
    )
    (net (code "34") (name "Net-(U40B-IN-)") (class "Default")
      (node (ref "R181") (pin "1") (pinfunction "1_1") (pintype "passive"))
      (node (ref "U40") (pin "6") (pinfunction "IN-_6") (pintype "input"))
    )
    (net (code "35") (name "Net-(U41-OUT)") (class "Default")
      (node (ref "R70") (pin "1") (pinfunction "1_1") (pintype "passive"))
      (node (ref "U41") (pin "1") (pinfunction "OUT_1") (pintype "passive"))
    )
    (net (code "36") (name "Net-(U42A-1B)") (class "Default")
      (node (ref "U42") (pin "10") (pinfunction "3B_10") (pintype "input"))
      (node (ref "U42") (pin "11") (pinfunction "4Y_11") (pintype "output"))
      (node (ref "U42") (pin "2") (pinfunction "1B_2") (pintype "input"))
    )
    (net (code "37") (name "Net-(U42C-3A)") (class "Default")
      (node (ref "C106") (pin "1") (pinfunction "1_1") (pintype "passive"))
      (node (ref "R42") (pin "1") (pinfunction "1_1") (pintype "passive"))
      (node (ref "U42") (pin "9") (pinfunction "3A_9") (pintype "input"))
    )
    (net (code "38") (name "Net-(U42C-3Y)") (class "Default")
      (node (ref "U42") (pin "13") (pinfunction "4B_13") (pintype "input"))
      (node (ref "U42") (pin "8") (pinfunction "3Y_8") (pintype "output"))
    )
    (net (code "39") (name "Net-(U50-CVOLT)") (class "Default")
      (node (ref "C142") (pin "2") (pinfunction "2_2") (pintype "passive"))
      (node (ref "U50") (pin "5") (pinfunction "CVOLT_5") (pintype "passive"))
    )
    (net (code "40") (name "Net-(U50-DISC)") (class "Default")
      (node (ref "C143") (pin "2") (pinfunction "2_2") (pintype "passive"))
      (node (ref "R201") (pin "1") (pinfunction "1_1") (pintype "passive"))
      (node (ref "U50") (pin "6") (pinfunction "THR_6") (pintype "input"))
      (node (ref "U50") (pin "7") (pinfunction "DISC_7") (pintype "open_collector"))
    )
    (net (code "41") (name "Net-(U50-TRIG)") (class "Default")
      (node (ref "C141") (pin "1") (pinfunction "1_1") (pintype "passive"))
      (node (ref "R200") (pin "1") (pinfunction "1_1") (pintype "passive"))
      (node (ref "U50") (pin "2") (pinfunction "TRIG_2") (pintype "input"))
    )
    (net (code "42") (name "unconnected-(K2-NC-Pad87a)") (class "Default")
      (node (ref "K2") (pin "87a") (pinfunction "NC_87a") (pintype "passive"))
    )
  )
)
